# EEPROM_DIP_Breakout_Jumper.net
KiCad netlist of a schematic drawn in EAGLE
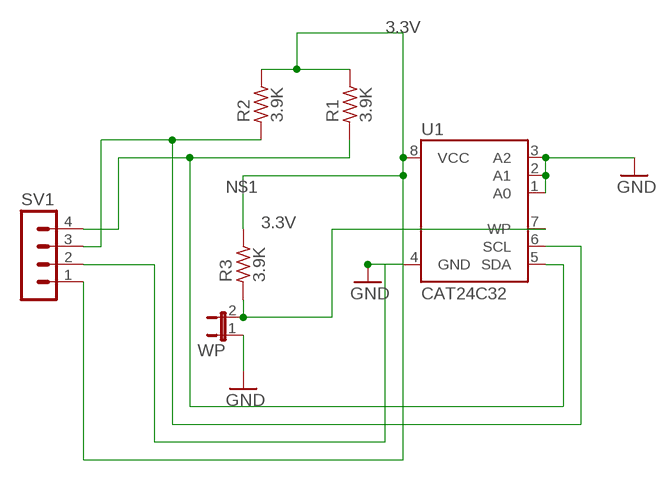
[diagram p0: schematic, sheet 1]

(export (version "E")
  (design (tool "Eeschema 10.0.6"))
  (components
    (comp (ref "R1")
      (value "3.9K")
      (footprint "eagle-import:0204_7")
      (libsource (lib "eagle-import") (part "R_X0204/7"))
    )
    (comp (ref "R2")
      (value "3.9K")
      (footprint "eagle-import:0204_7")
      (libsource (lib "eagle-import") (part "R_X0204/7"))
    )
    (comp (ref "R3")
      (value "3.9K")
      (footprint "eagle-import:0204_7")
      (libsource (lib "eagle-import") (part "R_X0204/7"))
    )
    (comp (ref "SV1")
      (value "MA04-1")
      (footprint "eagle-import:MA04-1")
      (libsource (lib "eagle-import") (part "MA04-1"))
    )
    (comp (ref "U1")
      (value "CAT24C32")
      (footprint "eagle-import:DIL08")
      (fields (field (name "MPN") "AT24C1024BW-SH-B"))
      (libsource (lib "eagle-import") (part "AT24CP"))
    )
    (comp (ref "WP")
      (value "JP1E")
      (footprint "eagle-import:JP1")
      (libsource (lib "eagle-import") (part "JP1E"))
    )
  )
  (nets
    (net (code "1") (name "/3.3V") (class "Default")
      (node (ref "R1") (pin "2") (pinfunction "2_2") (pintype "passive"))
      (node (ref "R2") (pin "2") (pinfunction "2_2") (pintype "passive"))
      (node (ref "R3") (pin "2") (pinfunction "2_2") (pintype "passive"))
      (node (ref "SV1") (pin "1") (pinfunction "1_1") (pintype "passive"))
      (node (ref "U1") (pin "8") (pinfunction "VCC_8") (pintype "power_in"))
    )
    (net (code "2") (name "/N$1") (class "Default")
      (node (ref "R1") (pin "1") (pinfunction "1_1") (pintype "passive"))
      (node (ref "SV1") (pin "4") (pinfunction "4_4") (pintype "passive"))
      (node (ref "U1") (pin "5") (pinfunction "SDA_5") (pintype "bidirectional"))
    )
    (net (code "3") (name "GND") (class "Default")
      (node (ref "SV1") (pin "2") (pinfunction "2_2") (pintype "passive"))
      (node (ref "U1") (pin "1") (pinfunction "A0_1") (pintype "input"))
      (node (ref "U1") (pin "2") (pinfunction "A1_2") (pintype "input"))
      (node (ref "U1") (pin "3") (pinfunction "A2_3") (pintype "input"))
      (node (ref "U1") (pin "4") (pinfunction "GND_4") (pintype "power_in"))
      (node (ref "WP") (pin "1") (pinfunction "1_1") (pintype "passive"))
    )
    (net (code "4") (name "Net-(U1-SCL)") (class "Default")
      (node (ref "R2") (pin "1") (pinfunction "1_1") (pintype "passive"))
      (node (ref "SV1") (pin "3") (pinfunction "3_3") (pintype "passive"))
      (node (ref "U1") (pin "6") (pinfunction "SCL_6") (pintype "bidirectional"))
    )
    (net (code "5") (name "Net-(U1-WP)") (class "Default")
      (node (ref "R3") (pin "1") (pinfunction "1_1") (pintype "passive"))
      (node (ref "U1") (pin "7") (pinfunction "WP_7") (pintype "input"))
      (node (ref "WP") (pin "2") (pinfunction "2_2") (pintype "passive"))
    )
  )
)
